# ATMEGA328_SUBSYSTEM.net
KiCad netlist of a schematic drawn in EAGLE
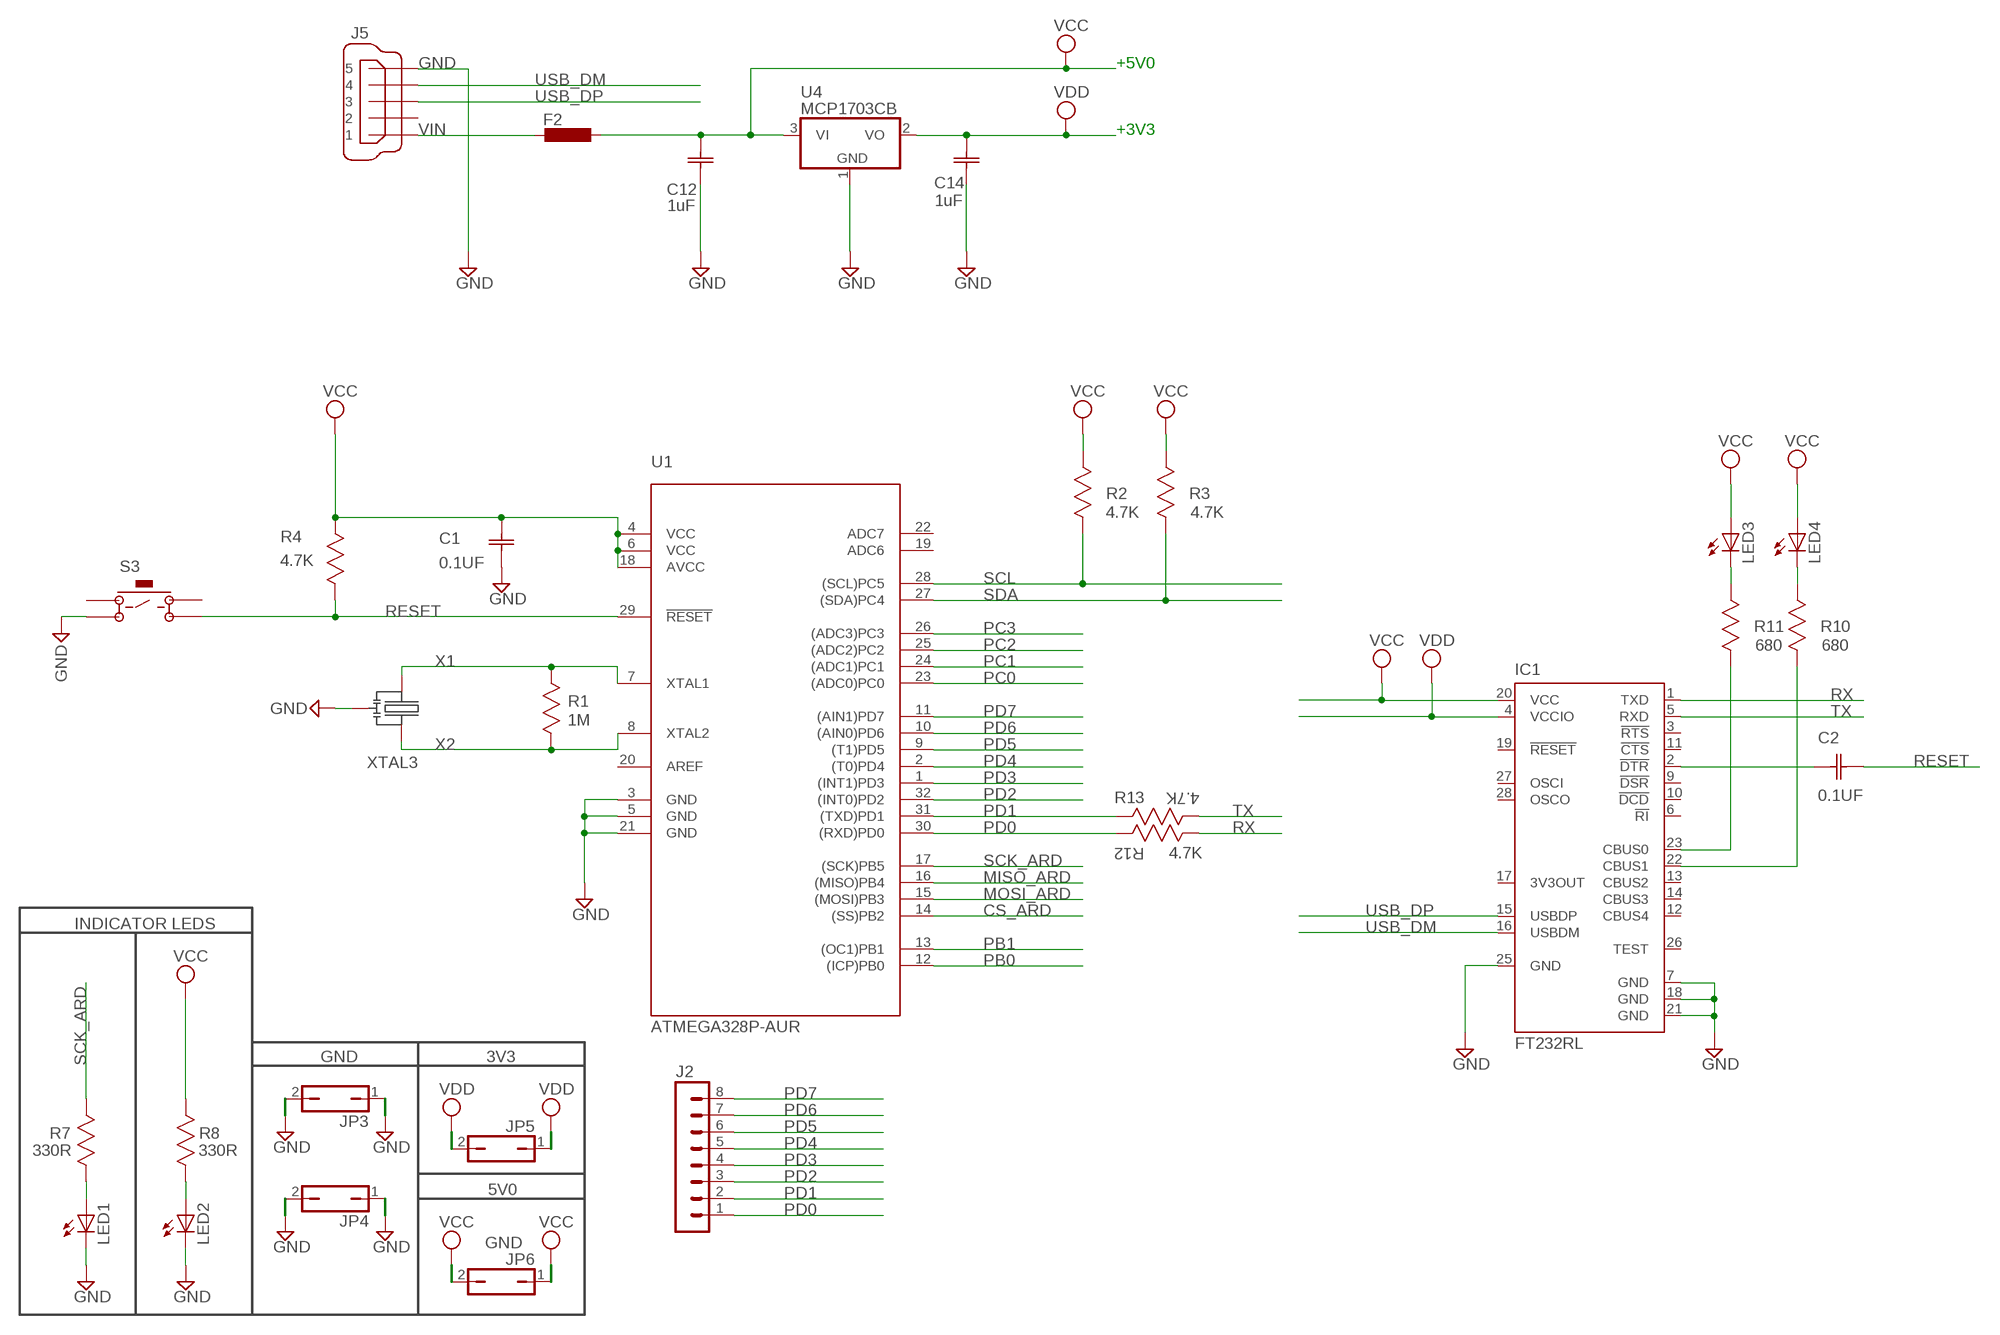
[diagram p0: schematic, sheet 1]

(export (version "E")
  (design (tool "Eeschema 10.0.6"))
  (components
    (comp (ref "C1")
      (value "0.1UF")
      (footprint "eagle-import:CAPC1608X90N")
      (fields (field (name "MPN") "0603ZC104KA72A") (field (name "TOLERANCE") "±10%"))
      (libsource (lib "eagle-import") (part "0603ZC104KA72A"))
    )
    (comp (ref "C2")
      (value "0.1UF")
      (footprint "eagle-import:CAPC1608X90N")
      (fields (field (name "MPN") "0603ZC104KA72A") (field (name "TOLERANCE") "±10%"))
      (libsource (lib "eagle-import") (part "0603ZC104KA72A"))
    )
    (comp (ref "C12")
      (value "1uF")
      (footprint "eagle-import:CAPC2013X140N")
      (fields (field (name "MPN") "C0805C105K3RACTU") (field (name "TOLERANCE") "±10%"))
      (libsource (lib "eagle-import") (part "C0805C105K3RACTU"))
    )
    (comp (ref "C14")
      (value "1uF")
      (footprint "eagle-import:CAPC2013X140N")
      (fields (field (name "MPN") "C0805C105K3RACTU") (field (name "TOLERANCE") "±10%"))
      (libsource (lib "eagle-import") (part "C0805C105K3RACTU"))
    )
    (comp (ref "F2")
      (value "L-EUL1812")
      (footprint "eagle-import:L1812")
      (libsource (lib "eagle-import") (part "L-EUL1812"))
    )
    (comp (ref "IC1")
      (value "FT232RL")
      (footprint "eagle-import:SSOP28")
      (libsource (lib "eagle-import") (part "FT232RL"))
    )
    (comp (ref "J2")
      (value "MA08-1")
      (footprint "eagle-import:MA08-1")
      (libsource (lib "eagle-import") (part "MA08-1"))
    )
    (comp (ref "J5")
      (value "MINI-USB-UX60A-MB-5ST")
      (footprint "eagle-import:UX60A-MB-5ST")
      (libsource (lib "eagle-import") (part "MINI-USB-UX60A-MB-5ST"))
    )
    (comp (ref "JP3")
      (value "JP1Q")
      (footprint "eagle-import:JP1")
      (libsource (lib "eagle-import") (part "JP1Q"))
    )
    (comp (ref "JP4")
      (value "JP1Q")
      (footprint "eagle-import:JP1")
      (libsource (lib "eagle-import") (part "JP1Q"))
    )
    (comp (ref "JP5")
      (value "JP1Q")
      (footprint "eagle-import:JP1")
      (libsource (lib "eagle-import") (part "JP1Q"))
    )
    (comp (ref "JP6")
      (value "JP1Q")
      (footprint "eagle-import:JP1")
      (libsource (lib "eagle-import") (part "JP1Q"))
    )
    (comp (ref "LED1")
      (value "LEDCHIP-LED0603")
      (footprint "eagle-import:CHIP-LED0603")
      (libsource (lib "eagle-import") (part "led_LEDCHIP-LED0603"))
    )
    (comp (ref "LED2")
      (value "LEDCHIP-LED0603")
      (footprint "eagle-import:CHIP-LED0603")
      (libsource (lib "eagle-import") (part "led_LEDCHIP-LED0603"))
    )
    (comp (ref "LED3")
      (value "LEDCHIPLED_0805")
      (footprint "eagle-import:CHIPLED_0805")
      (libsource (lib "eagle-import") (part "LEDCHIPLED_0805"))
    )
    (comp (ref "LED4")
      (value "LEDCHIPLED_0805")
      (footprint "eagle-import:CHIPLED_0805")
      (libsource (lib "eagle-import") (part "LEDCHIPLED_0805"))
    )
    (comp (ref "R1")
      (value "1M")
      (footprint "eagle-import:RESC1608X60N")
      (fields (field (name "MPN") "MC0.063W06031%1M") (field (name "TOLERANCE") "1%"))
      (libsource (lib "eagle-import") (part "MC0.063W06031%1M"))
    )
    (comp (ref "R2")
      (value "4.7K")
      (footprint "eagle-import:RESC1608X60N")
      (fields (field (name "MPN") "MC0.063W06031%4K7") (field (name "TOLERANCE") "1%"))
      (libsource (lib "eagle-import") (part "MC0.063W06031%4K7"))
    )
    (comp (ref "R3")
      (value "4.7K")
      (footprint "eagle-import:RESC1608X60N")
      (fields (field (name "MPN") "MC0.063W06031%4K7") (field (name "TOLERANCE") "1%"))
      (libsource (lib "eagle-import") (part "MC0.063W06031%4K7"))
    )
    (comp (ref "R4")
      (value "4.7K")
      (footprint "eagle-import:RESC1608X60N")
      (fields (field (name "MPN") "MC0.063W06031%4K7") (field (name "TOLERANCE") "1%"))
      (libsource (lib "eagle-import") (part "MC0.063W06031%4K7"))
    )
    (comp (ref "R7")
      (value "330R")
      (footprint "eagle-import:RESC1608X60N")
      (fields (field (name "MPN") "MC0.063W06031%330R") (field (name "TOLERANCE") "±1%"))
      (libsource (lib "eagle-import") (part "MC0.063W06031%330R"))
    )
    (comp (ref "R8")
      (value "330R")
      (footprint "eagle-import:RESC1608X60N")
      (fields (field (name "MPN") "MC0.063W06031%330R") (field (name "TOLERANCE") "±1%"))
      (libsource (lib "eagle-import") (part "MC0.063W06031%330R"))
    )
    (comp (ref "R10")
      (value "680")
      (footprint "eagle-import:RESC1608X60N")
      (fields (field (name "MPN") "MC0.063W06031%4K7") (field (name "TOLERANCE") "1%"))
      (libsource (lib "eagle-import") (part "MC0.063W06031%4K7"))
    )
    (comp (ref "R11")
      (value "680")
      (footprint "eagle-import:RESC1608X60N")
      (fields (field (name "MPN") "MC0.063W06031%4K7") (field (name "TOLERANCE") "1%"))
      (libsource (lib "eagle-import") (part "MC0.063W06031%4K7"))
    )
    (comp (ref "R12")
      (value "4.7K")
      (footprint "eagle-import:RESC1608X60N")
      (fields (field (name "MPN") "MC0.063W06031%4K7") (field (name "TOLERANCE") "1%"))
      (libsource (lib "eagle-import") (part "MC0.063W06031%4K7"))
    )
    (comp (ref "R13")
      (value "4.7K")
      (footprint "eagle-import:RESC1608X60N")
      (fields (field (name "MPN") "MC0.063W06031%4K7") (field (name "TOLERANCE") "1%"))
      (libsource (lib "eagle-import") (part "MC0.063W06031%4K7"))
    )
    (comp (ref "S3")
      (value "1825910-6-SPST-NOPB-4P")
      (footprint "eagle-import:SW-NOPB-4")
      (libsource (lib "eagle-import") (part "1825910-6-SPST-NOPB-4P"))
    )
    (comp (ref "U1")
      (value "ATMEGA328P-AUR")
      (footprint "eagle-import:TQFP-32")
      (fields (field (name "MANUFACTURER") "ATMEL"))
      (libsource (lib "eagle-import") (part "ATMEGA328P-AUR"))
    )
    (comp (ref "U4")
      (value "MCP1703CB")
      (footprint "eagle-import:SOT23")
      (libsource (lib "eagle-import") (part "MCP1703CB"))
    )
    (comp (ref "XTAL3")
      (value "CSTCE16M0V53-R0")
      (footprint "eagle-import:CSTCE16M0V53-R0")
      (libsource (lib "eagle-import") (part "CSTCE16M0V53-R0"))
    )
  )
  (nets
    (net (code "1") (name "/CS_ARD") (class "Default")
      (node (ref "U1") (pin "14") (pinfunction "(SS)PB2_14") (pintype "bidirectional"))
    )
    (net (code "2") (name "/MISO_ARD") (class "Default")
      (node (ref "U1") (pin "16") (pinfunction "(MISO)PB4_16") (pintype "bidirectional"))
    )
    (net (code "3") (name "/MOSI_ARD") (class "Default")
      (node (ref "U1") (pin "15") (pinfunction "(MOSI)PB3_15") (pintype "bidirectional"))
    )
    (net (code "4") (name "/PB0") (class "Default")
      (node (ref "U1") (pin "12") (pinfunction "(ICP)PB0_12") (pintype "bidirectional"))
    )
    (net (code "5") (name "/PB1") (class "Default")
      (node (ref "U1") (pin "13") (pinfunction "(OC1)PB1_13") (pintype "bidirectional"))
    )
    (net (code "6") (name "/PC0") (class "Default")
      (node (ref "U1") (pin "23") (pinfunction "(ADC0)PC0_23") (pintype "bidirectional"))
    )
    (net (code "7") (name "/PC1") (class "Default")
      (node (ref "U1") (pin "24") (pinfunction "(ADC1)PC1_24") (pintype "bidirectional"))
    )
    (net (code "8") (name "/PC2") (class "Default")
      (node (ref "U1") (pin "25") (pinfunction "(ADC2)PC2_25") (pintype "bidirectional"))
    )
    (net (code "9") (name "/PC3") (class "Default")
      (node (ref "U1") (pin "26") (pinfunction "(ADC3)PC3_26") (pintype "bidirectional"))
    )
    (net (code "10") (name "/PD0") (class "Default")
      (node (ref "J2") (pin "1") (pinfunction "1_1") (pintype "passive"))
      (node (ref "R12") (pin "1") (pinfunction "R1_1") (pintype "passive"))
      (node (ref "U1") (pin "30") (pinfunction "(RXD)PD0_30") (pintype "bidirectional"))
    )
    (net (code "11") (name "/PD1") (class "Default")
      (node (ref "J2") (pin "2") (pinfunction "2_2") (pintype "passive"))
      (node (ref "R13") (pin "1") (pinfunction "R1_1") (pintype "passive"))
      (node (ref "U1") (pin "31") (pinfunction "(TXD)PD1_31") (pintype "bidirectional"))
    )
    (net (code "12") (name "/PD2") (class "Default")
      (node (ref "J2") (pin "3") (pinfunction "3_3") (pintype "passive"))
      (node (ref "U1") (pin "32") (pinfunction "(INT0)PD2_32") (pintype "bidirectional"))
    )
    (net (code "13") (name "/PD3") (class "Default")
      (node (ref "J2") (pin "4") (pinfunction "4_4") (pintype "passive"))
      (node (ref "U1") (pin "1") (pinfunction "(INT1)PD3_1") (pintype "bidirectional"))
    )
    (net (code "14") (name "/PD4") (class "Default")
      (node (ref "J2") (pin "5") (pinfunction "5_5") (pintype "passive"))
      (node (ref "U1") (pin "2") (pinfunction "(T0)PD4_2") (pintype "bidirectional"))
    )
    (net (code "15") (name "/PD5") (class "Default")
      (node (ref "J2") (pin "6") (pinfunction "6_6") (pintype "passive"))
      (node (ref "U1") (pin "9") (pinfunction "(T1)PD5_9") (pintype "bidirectional"))
    )
    (net (code "16") (name "/PD6") (class "Default")
      (node (ref "J2") (pin "7") (pinfunction "7_7") (pintype "passive"))
      (node (ref "U1") (pin "10") (pinfunction "(AIN0)PD6_10") (pintype "bidirectional"))
    )
    (net (code "17") (name "/PD7") (class "Default")
      (node (ref "J2") (pin "8") (pinfunction "8_8") (pintype "passive"))
      (node (ref "U1") (pin "11") (pinfunction "(AIN1)PD7_11") (pintype "bidirectional"))
    )
    (net (code "18") (name "/RESET") (class "Default")
      (node (ref "C2") (pin "1") (pinfunction "C1_1") (pintype "passive"))
      (node (ref "R4") (pin "2") (pinfunction "R2_2") (pintype "passive"))
      (node (ref "S3") (pin "4") (pinfunction "4_4") (pintype "bidirectional"))
      (node (ref "U1") (pin "29") (pinfunction "~{RESET}_29") (pintype "bidirectional"))
    )
    (net (code "19") (name "/RX") (class "Default")
      (node (ref "IC1") (pin "1") (pinfunction "TXD_1") (pintype "output"))
      (node (ref "R12") (pin "2") (pinfunction "R2_2") (pintype "passive"))
    )
    (net (code "20") (name "/SCK_ARD") (class "Default")
      (node (ref "R7") (pin "1") (pinfunction "R1_1") (pintype "passive"))
      (node (ref "U1") (pin "17") (pinfunction "(SCK)PB5_17") (pintype "bidirectional"))
    )
    (net (code "21") (name "/SCL") (class "Default")
      (node (ref "R2") (pin "2") (pinfunction "R2_2") (pintype "passive"))
      (node (ref "U1") (pin "28") (pinfunction "(SCL)PC5_28") (pintype "bidirectional"))
    )
    (net (code "22") (name "/SDA") (class "Default")
      (node (ref "R3") (pin "2") (pinfunction "R2_2") (pintype "passive"))
      (node (ref "U1") (pin "27") (pinfunction "(SDA)PC4_27") (pintype "bidirectional"))
    )
    (net (code "23") (name "/TX") (class "Default")
      (node (ref "IC1") (pin "5") (pinfunction "RXD_5") (pintype "input"))
      (node (ref "R13") (pin "2") (pinfunction "R2_2") (pintype "passive"))
    )
    (net (code "24") (name "/USB_DM") (class "Default")
      (node (ref "IC1") (pin "16") (pinfunction "USBDM_16") (pintype "bidirectional"))
      (node (ref "J5") (pin "4") (pinfunction "4_4") (pintype "input"))
    )
    (net (code "25") (name "/USB_DP") (class "Default")
      (node (ref "IC1") (pin "15") (pinfunction "USBDP_15") (pintype "bidirectional"))
      (node (ref "J5") (pin "3") (pinfunction "3_3") (pintype "input"))
    )
    (net (code "26") (name "/VIN") (class "Default")
      (node (ref "F2") (pin "2") (pinfunction "2_2") (pintype "passive"))
      (node (ref "J5") (pin "1") (pinfunction "1_1") (pintype "input"))
    )
    (net (code "27") (name "/X1") (class "Default")
      (node (ref "R1") (pin "2") (pinfunction "R2_2") (pintype "passive"))
      (node (ref "U1") (pin "7") (pinfunction "XTAL1_7") (pintype "bidirectional"))
      (node (ref "XTAL3") (pin "1") (pinfunction "1_1") (pintype "bidirectional"))
    )
    (net (code "28") (name "/X2") (class "Default")
      (node (ref "R1") (pin "1") (pinfunction "R1_1") (pintype "passive"))
      (node (ref "U1") (pin "8") (pinfunction "XTAL2_8") (pintype "bidirectional"))
      (node (ref "XTAL3") (pin "3") (pinfunction "3_3") (pintype "bidirectional"))
    )
    (net (code "29") (name "GND") (class "Default")
      (node (ref "C1") (pin "1") (pinfunction "C1_1") (pintype "passive"))
      (node (ref "C12") (pin "1") (pinfunction "C1_1") (pintype "passive"))
      (node (ref "C14") (pin "1") (pinfunction "C1_1") (pintype "passive"))
      (node (ref "IC1") (pin "18") (pinfunction "GND_18") (pintype "power_in"))
      (node (ref "IC1") (pin "21") (pinfunction "GND_21") (pintype "power_in"))
      (node (ref "IC1") (pin "25") (pinfunction "GND_25") (pintype "power_in"))
      (node (ref "IC1") (pin "7") (pinfunction "GND_7") (pintype "power_in"))
      (node (ref "J5") (pin "5") (pinfunction "5_5") (pintype "input"))
      (node (ref "JP3") (pin "1") (pinfunction "1_1") (pintype "passive"))
      (node (ref "JP3") (pin "2") (pinfunction "2_2") (pintype "passive"))
      (node (ref "JP4") (pin "1") (pinfunction "1_1") (pintype "passive"))
      (node (ref "JP4") (pin "2") (pinfunction "2_2") (pintype "passive"))
      (node (ref "LED1") (pin "C") (pinfunction "C_C") (pintype "passive"))
      (node (ref "LED2") (pin "C") (pinfunction "C_C") (pintype "passive"))
      (node (ref "S3") (pin "2") (pinfunction "2_2") (pintype "bidirectional"))
      (node (ref "U1") (pin "21") (pinfunction "GND_21") (pintype "bidirectional"))
      (node (ref "U1") (pin "3") (pinfunction "GND_3") (pintype "bidirectional"))
      (node (ref "U1") (pin "5") (pinfunction "GND_5") (pintype "bidirectional"))
      (node (ref "U4") (pin "1") (pinfunction "GND_1") (pintype "passive"))
      (node (ref "XTAL3") (pin "2") (pinfunction "2_2") (pintype "bidirectional"))
    )
    (net (code "30") (name "Net-(C2-C2)") (class "Default")
      (node (ref "C2") (pin "2") (pinfunction "C2_2") (pintype "passive"))
      (node (ref "IC1") (pin "2") (pinfunction "~{DTR}_2") (pintype "output"))
    )
    (net (code "31") (name "Net-(IC1-CBUS0)") (class "Default")
      (node (ref "IC1") (pin "23") (pinfunction "CBUS0_23") (pintype "bidirectional"))
      (node (ref "R11") (pin "2") (pinfunction "R2_2") (pintype "passive"))
    )
    (net (code "32") (name "Net-(IC1-CBUS1)") (class "Default")
      (node (ref "IC1") (pin "22") (pinfunction "CBUS1_22") (pintype "bidirectional"))
      (node (ref "R10") (pin "2") (pinfunction "R2_2") (pintype "passive"))
    )
    (net (code "33") (name "Net-(R7-R2)") (class "Default")
      (node (ref "LED1") (pin "A") (pinfunction "A_A") (pintype "passive"))
      (node (ref "R7") (pin "2") (pinfunction "R2_2") (pintype "passive"))
    )
    (net (code "34") (name "Net-(R8-R2)") (class "Default")
      (node (ref "LED2") (pin "A") (pinfunction "A_A") (pintype "passive"))
      (node (ref "R8") (pin "2") (pinfunction "R2_2") (pintype "passive"))
    )
    (net (code "35") (name "Net-(R10-R1)") (class "Default")
      (node (ref "LED4") (pin "C") (pinfunction "C_C") (pintype "passive"))
      (node (ref "R10") (pin "1") (pinfunction "R1_1") (pintype "passive"))
    )
    (net (code "36") (name "Net-(R11-R1)") (class "Default")
      (node (ref "LED3") (pin "C") (pinfunction "C_C") (pintype "passive"))
      (node (ref "R11") (pin "1") (pinfunction "R1_1") (pintype "passive"))
    )
    (net (code "37") (name "VCC") (class "Default")
      (node (ref "C1") (pin "2") (pinfunction "C2_2") (pintype "passive"))
      (node (ref "C12") (pin "2") (pinfunction "C2_2") (pintype "passive"))
      (node (ref "F2") (pin "1") (pinfunction "1_1") (pintype "passive"))
      (node (ref "IC1") (pin "20") (pinfunction "VCC_20") (pintype "power_in"))
      (node (ref "JP6") (pin "1") (pinfunction "1_1") (pintype "passive"))
      (node (ref "JP6") (pin "2") (pinfunction "2_2") (pintype "passive"))
      (node (ref "LED3") (pin "A") (pinfunction "A_A") (pintype "passive"))
      (node (ref "LED4") (pin "A") (pinfunction "A_A") (pintype "passive"))
      (node (ref "R2") (pin "1") (pinfunction "R1_1") (pintype "passive"))
      (node (ref "R3") (pin "1") (pinfunction "R1_1") (pintype "passive"))
      (node (ref "R4") (pin "1") (pinfunction "R1_1") (pintype "passive"))
      (node (ref "R8") (pin "1") (pinfunction "R1_1") (pintype "passive"))
      (node (ref "U1") (pin "18") (pinfunction "AVCC_18") (pintype "bidirectional"))
      (node (ref "U1") (pin "4") (pinfunction "VCC_4") (pintype "bidirectional"))
      (node (ref "U1") (pin "6") (pinfunction "VCC_6") (pintype "bidirectional"))
      (node (ref "U4") (pin "3") (pinfunction "VI_3") (pintype "input"))
    )
    (net (code "38") (name "VDD") (class "Default")
      (node (ref "C14") (pin "2") (pinfunction "C2_2") (pintype "passive"))
      (node (ref "IC1") (pin "4") (pinfunction "VCCIO_4") (pintype "power_in"))
      (node (ref "JP5") (pin "1") (pinfunction "1_1") (pintype "passive"))
      (node (ref "JP5") (pin "2") (pinfunction "2_2") (pintype "passive"))
      (node (ref "U4") (pin "2") (pinfunction "VO_2") (pintype "passive"))
    )
    (net (code "39") (name "unconnected-(IC1-3V3OUT-Pad17)") (class "Default")
      (node (ref "IC1") (pin "17") (pinfunction "3V3OUT_17") (pintype "output"))
    )
    (net (code "40") (name "unconnected-(IC1-CBUS2-Pad13)") (class "Default")
      (node (ref "IC1") (pin "13") (pinfunction "CBUS2_13") (pintype "bidirectional"))
    )
    (net (code "41") (name "unconnected-(IC1-CBUS3-Pad14)") (class "Default")
      (node (ref "IC1") (pin "14") (pinfunction "CBUS3_14") (pintype "bidirectional"))
    )
    (net (code "42") (name "unconnected-(IC1-CBUS4-Pad12)") (class "Default")
      (node (ref "IC1") (pin "12") (pinfunction "CBUS4_12") (pintype "bidirectional"))
    )
    (net (code "43") (name "unconnected-(IC1-OSCI-Pad27)") (class "Default")
      (node (ref "IC1") (pin "27") (pinfunction "OSCI_27") (pintype "input"))
    )
    (net (code "44") (name "unconnected-(IC1-OSCO-Pad28)") (class "Default")
      (node (ref "IC1") (pin "28") (pinfunction "OSCO_28") (pintype "output"))
    )
    (net (code "45") (name "unconnected-(IC1-TEST-Pad26)") (class "Default")
      (node (ref "IC1") (pin "26") (pinfunction "TEST_26") (pintype "input"))
    )
    (net (code "46") (name "unconnected-(IC1-~{CTS}-Pad11)") (class "Default")
      (node (ref "IC1") (pin "11") (pinfunction "~{CTS}_11") (pintype "input"))
    )
    (net (code "47") (name "unconnected-(IC1-~{DCD}-Pad10)") (class "Default")
      (node (ref "IC1") (pin "10") (pinfunction "~{DCD}_10") (pintype "input"))
    )
    (net (code "48") (name "unconnected-(IC1-~{DSR}-Pad9)") (class "Default")
      (node (ref "IC1") (pin "9") (pinfunction "~{DSR}_9") (pintype "input"))
    )
    (net (code "49") (name "unconnected-(IC1-~{RESET}-Pad19)") (class "Default")
      (node (ref "IC1") (pin "19") (pinfunction "~{RESET}_19") (pintype "input"))
    )
    (net (code "50") (name "unconnected-(IC1-~{RI}-Pad6)") (class "Default")
      (node (ref "IC1") (pin "6") (pinfunction "~{RI}_6") (pintype "input"))
    )
    (net (code "51") (name "unconnected-(IC1-~{RTS}-Pad3)") (class "Default")
      (node (ref "IC1") (pin "3") (pinfunction "~{RTS}_3") (pintype "output"))
    )
    (net (code "52") (name "unconnected-(J5-Pad2)") (class "Default")
      (node (ref "J5") (pin "2") (pinfunction "2_2") (pintype "input"))
    )
    (net (code "53") (name "unconnected-(S3-Pad1)") (class "Default")
      (node (ref "S3") (pin "1") (pinfunction "1_1") (pintype "bidirectional"))
    )
    (net (code "54") (name "unconnected-(S3-Pad3)") (class "Default")
      (node (ref "S3") (pin "3") (pinfunction "3_3") (pintype "bidirectional"))
    )
    (net (code "55") (name "unconnected-(U1-ADC6-Pad19)") (class "Default")
      (node (ref "U1") (pin "19") (pinfunction "ADC6_19") (pintype "bidirectional"))
    )
    (net (code "56") (name "unconnected-(U1-ADC7-Pad22)") (class "Default")
      (node (ref "U1") (pin "22") (pinfunction "ADC7_22") (pintype "bidirectional"))
    )
    (net (code "57") (name "unconnected-(U1-AREF-Pad20)") (class "Default")
      (node (ref "U1") (pin "20") (pinfunction "AREF_20") (pintype "bidirectional"))
    )
  )
)
